# FY_-_OPTO_BOARD_1_SWBOTTOP.net
KiCad netlist of a schematic drawn in EAGLE
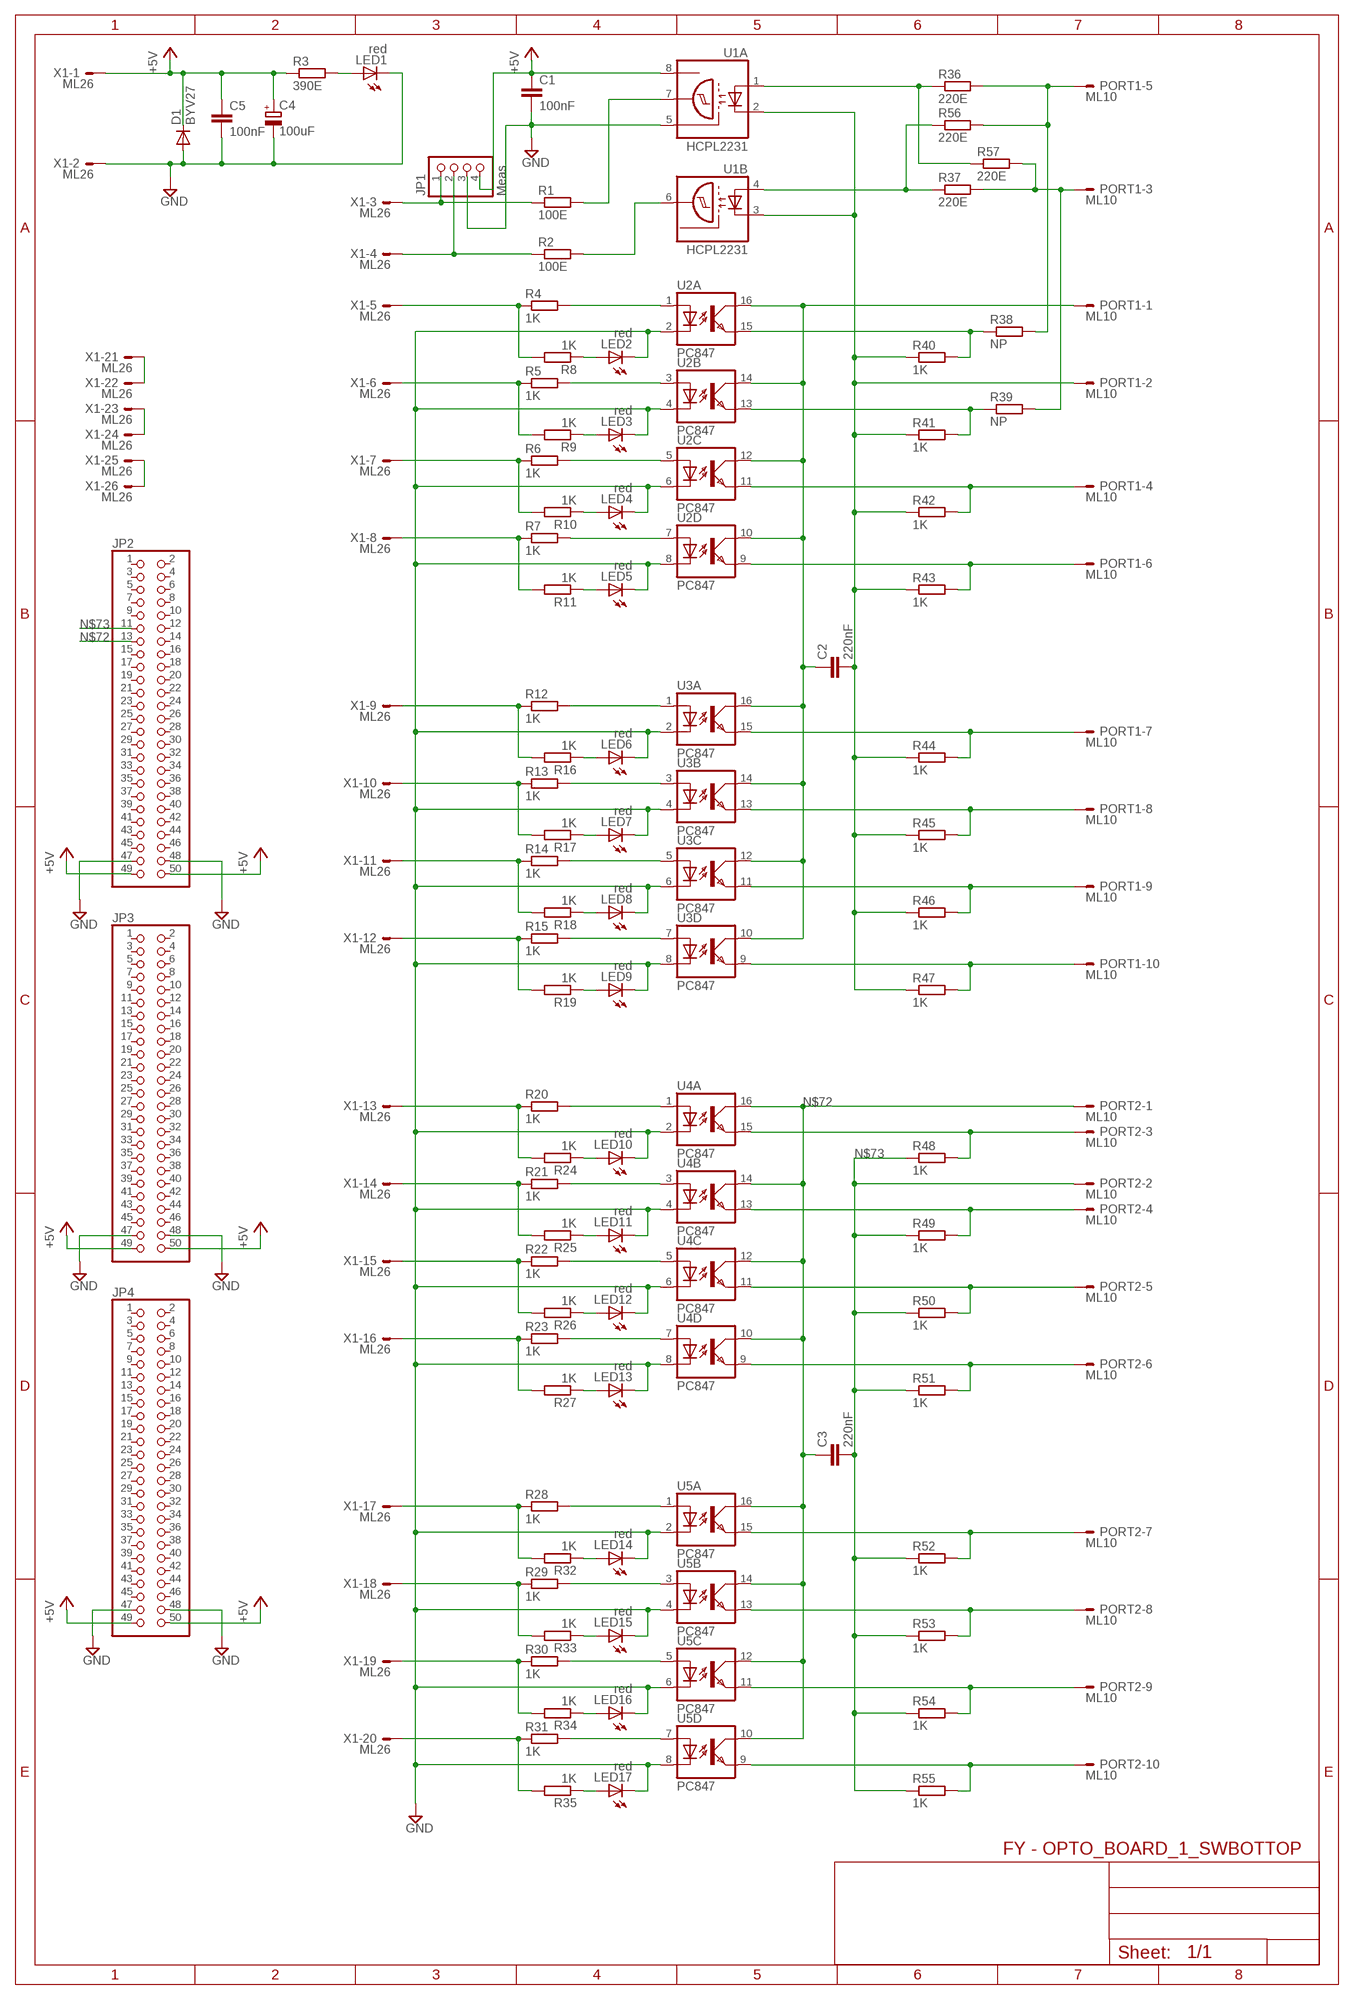
[diagram p0: schematic, sheet 1]

(export (version "E")
  (design (tool "Eeschema 10.0.6"))
  (components
    (comp (ref "C1")
      (value "100nF")
      (footprint "eagle-import:C050-025X075")
      (libsource (lib "eagle-import") (part "C-EU050-025X075"))
    )
    (comp (ref "C2")
      (value "220nF")
      (footprint "eagle-import:C050-025X075")
      (libsource (lib "eagle-import") (part "C-EU050-025X075"))
    )
    (comp (ref "C3")
      (value "220nF")
      (footprint "eagle-import:C050-025X075")
      (libsource (lib "eagle-import") (part "C-EU050-025X075"))
    )
    (comp (ref "C4")
      (value "100uF")
      (footprint "eagle-import:E5-8,5")
      (libsource (lib "eagle-import") (part "CPOL-EUE5-8.5"))
    )
    (comp (ref "C5")
      (value "100nF")
      (footprint "eagle-import:C050-025X075")
      (libsource (lib "eagle-import") (part "C-EU050-025X075"))
    )
    (comp (ref "D1")
      (value "BYV27")
      (footprint "eagle-import:SOD57-10")
      (libsource (lib "eagle-import") (part "BYV27"))
    )
    (comp (ref "JP1")
      (value "Meas")
      (footprint "eagle-import:1X04")
      (libsource (lib "eagle-import") (part "PINHD-1X4"))
    )
    (comp (ref "JP2")
      (value "PINHD-2X25")
      (footprint "eagle-import:2X25")
      (libsource (lib "eagle-import") (part "PINHD-2X25"))
    )
    (comp (ref "JP3")
      (value "PINHD-2X25")
      (footprint "eagle-import:2X25")
      (libsource (lib "eagle-import") (part "PINHD-2X25"))
    )
    (comp (ref "JP4")
      (value "PINHD-2X25")
      (footprint "eagle-import:2X25")
      (libsource (lib "eagle-import") (part "PINHD-2X25"))
    )
    (comp (ref "LED1")
      (value "red")
      (footprint "eagle-import:LED3MM")
      (libsource (lib "eagle-import") (part "LED3MM"))
    )
    (comp (ref "LED2")
      (value "red")
      (footprint "eagle-import:LED3MM")
      (libsource (lib "eagle-import") (part "LED3MM"))
    )
    (comp (ref "LED3")
      (value "red")
      (footprint "eagle-import:LED3MM")
      (libsource (lib "eagle-import") (part "LED3MM"))
    )
    (comp (ref "LED4")
      (value "red")
      (footprint "eagle-import:LED3MM")
      (libsource (lib "eagle-import") (part "LED3MM"))
    )
    (comp (ref "LED5")
      (value "red")
      (footprint "eagle-import:LED3MM")
      (libsource (lib "eagle-import") (part "LED3MM"))
    )
    (comp (ref "LED6")
      (value "red")
      (footprint "eagle-import:LED3MM")
      (libsource (lib "eagle-import") (part "LED3MM"))
    )
    (comp (ref "LED7")
      (value "red")
      (footprint "eagle-import:LED3MM")
      (libsource (lib "eagle-import") (part "LED3MM"))
    )
    (comp (ref "LED8")
      (value "red")
      (footprint "eagle-import:LED3MM")
      (libsource (lib "eagle-import") (part "LED3MM"))
    )
    (comp (ref "LED9")
      (value "red")
      (footprint "eagle-import:LED3MM")
      (libsource (lib "eagle-import") (part "LED3MM"))
    )
    (comp (ref "LED10")
      (value "red")
      (footprint "eagle-import:LED3MM")
      (libsource (lib "eagle-import") (part "LED3MM"))
    )
    (comp (ref "LED11")
      (value "red")
      (footprint "eagle-import:LED3MM")
      (libsource (lib "eagle-import") (part "LED3MM"))
    )
    (comp (ref "LED12")
      (value "red")
      (footprint "eagle-import:LED3MM")
      (libsource (lib "eagle-import") (part "LED3MM"))
    )
    (comp (ref "LED13")
      (value "red")
      (footprint "eagle-import:LED3MM")
      (libsource (lib "eagle-import") (part "LED3MM"))
    )
    (comp (ref "LED14")
      (value "red")
      (footprint "eagle-import:LED3MM")
      (libsource (lib "eagle-import") (part "LED3MM"))
    )
    (comp (ref "LED15")
      (value "red")
      (footprint "eagle-import:LED3MM")
      (libsource (lib "eagle-import") (part "LED3MM"))
    )
    (comp (ref "LED16")
      (value "red")
      (footprint "eagle-import:LED3MM")
      (libsource (lib "eagle-import") (part "LED3MM"))
    )
    (comp (ref "LED17")
      (value "red")
      (footprint "eagle-import:LED3MM")
      (libsource (lib "eagle-import") (part "LED3MM"))
    )
    (comp (ref "PORT1")
      (value "ML10")
      (footprint "eagle-import:ML10")
      (libsource (lib "eagle-import") (part "ML10?E"))
    )
    (comp (ref "PORT2")
      (value "ML10")
      (footprint "eagle-import:ML10")
      (libsource (lib "eagle-import") (part "ML10?E"))
    )
    (comp (ref "R1")
      (value "100E")
      (footprint "eagle-import:0207_10")
      (libsource (lib "eagle-import") (part "R-EU_0207/10"))
    )
    (comp (ref "R2")
      (value "100E")
      (footprint "eagle-import:0207_10")
      (libsource (lib "eagle-import") (part "R-EU_0207/10"))
    )
    (comp (ref "R3")
      (value "390E")
      (footprint "eagle-import:0207_10")
      (libsource (lib "eagle-import") (part "R-EU_0207/10"))
    )
    (comp (ref "R4")
      (value "1K")
      (footprint "eagle-import:0207_10")
      (libsource (lib "eagle-import") (part "R-EU_0207/10"))
    )
    (comp (ref "R5")
      (value "1K")
      (footprint "eagle-import:0207_10")
      (libsource (lib "eagle-import") (part "R-EU_0207/10"))
    )
    (comp (ref "R6")
      (value "1K")
      (footprint "eagle-import:0207_10")
      (libsource (lib "eagle-import") (part "R-EU_0207/10"))
    )
    (comp (ref "R7")
      (value "1K")
      (footprint "eagle-import:0207_10")
      (libsource (lib "eagle-import") (part "R-EU_0207/10"))
    )
    (comp (ref "R8")
      (value "1K")
      (footprint "eagle-import:0207_10")
      (libsource (lib "eagle-import") (part "R-EU_0207/10"))
    )
    (comp (ref "R9")
      (value "1K")
      (footprint "eagle-import:0207_10")
      (libsource (lib "eagle-import") (part "R-EU_0207/10"))
    )
    (comp (ref "R10")
      (value "1K")
      (footprint "eagle-import:0207_10")
      (libsource (lib "eagle-import") (part "R-EU_0207/10"))
    )
    (comp (ref "R11")
      (value "1K")
      (footprint "eagle-import:0207_10")
      (libsource (lib "eagle-import") (part "R-EU_0207/10"))
    )
    (comp (ref "R12")
      (value "1K")
      (footprint "eagle-import:0207_10")
      (libsource (lib "eagle-import") (part "R-EU_0207/10"))
    )
    (comp (ref "R13")
      (value "1K")
      (footprint "eagle-import:0207_10")
      (libsource (lib "eagle-import") (part "R-EU_0207/10"))
    )
    (comp (ref "R14")
      (value "1K")
      (footprint "eagle-import:0207_10")
      (libsource (lib "eagle-import") (part "R-EU_0207/10"))
    )
    (comp (ref "R15")
      (value "1K")
      (footprint "eagle-import:0207_10")
      (libsource (lib "eagle-import") (part "R-EU_0207/10"))
    )
    (comp (ref "R16")
      (value "1K")
      (footprint "eagle-import:0207_10")
      (libsource (lib "eagle-import") (part "R-EU_0207/10"))
    )
    (comp (ref "R17")
      (value "1K")
      (footprint "eagle-import:0207_10")
      (libsource (lib "eagle-import") (part "R-EU_0207/10"))
    )
    (comp (ref "R18")
      (value "1K")
      (footprint "eagle-import:0207_10")
      (libsource (lib "eagle-import") (part "R-EU_0207/10"))
    )
    (comp (ref "R19")
      (value "1K")
      (footprint "eagle-import:0207_10")
      (libsource (lib "eagle-import") (part "R-EU_0207/10"))
    )
    (comp (ref "R20")
      (value "1K")
      (footprint "eagle-import:0207_10")
      (libsource (lib "eagle-import") (part "R-EU_0207/10"))
    )
    (comp (ref "R21")
      (value "1K")
      (footprint "eagle-import:0207_10")
      (libsource (lib "eagle-import") (part "R-EU_0207/10"))
    )
    (comp (ref "R22")
      (value "1K")
      (footprint "eagle-import:0207_10")
      (libsource (lib "eagle-import") (part "R-EU_0207/10"))
    )
    (comp (ref "R23")
      (value "1K")
      (footprint "eagle-import:0207_10")
      (libsource (lib "eagle-import") (part "R-EU_0207/10"))
    )
    (comp (ref "R24")
      (value "1K")
      (footprint "eagle-import:0207_10")
      (libsource (lib "eagle-import") (part "R-EU_0207/10"))
    )
    (comp (ref "R25")
      (value "1K")
      (footprint "eagle-import:0207_10")
      (libsource (lib "eagle-import") (part "R-EU_0207/10"))
    )
    (comp (ref "R26")
      (value "1K")
      (footprint "eagle-import:0207_10")
      (libsource (lib "eagle-import") (part "R-EU_0207/10"))
    )
    (comp (ref "R27")
      (value "1K")
      (footprint "eagle-import:0207_10")
      (libsource (lib "eagle-import") (part "R-EU_0207/10"))
    )
    (comp (ref "R28")
      (value "1K")
      (footprint "eagle-import:0207_10")
      (libsource (lib "eagle-import") (part "R-EU_0207/10"))
    )
    (comp (ref "R29")
      (value "1K")
      (footprint "eagle-import:0207_10")
      (libsource (lib "eagle-import") (part "R-EU_0207/10"))
    )
    (comp (ref "R30")
      (value "1K")
      (footprint "eagle-import:0207_10")
      (libsource (lib "eagle-import") (part "R-EU_0207/10"))
    )
    (comp (ref "R31")
      (value "1K")
      (footprint "eagle-import:0207_10")
      (libsource (lib "eagle-import") (part "R-EU_0207/10"))
    )
    (comp (ref "R32")
      (value "1K")
      (footprint "eagle-import:0207_10")
      (libsource (lib "eagle-import") (part "R-EU_0207/10"))
    )
    (comp (ref "R33")
      (value "1K")
      (footprint "eagle-import:0207_10")
      (libsource (lib "eagle-import") (part "R-EU_0207/10"))
    )
    (comp (ref "R34")
      (value "1K")
      (footprint "eagle-import:0207_10")
      (libsource (lib "eagle-import") (part "R-EU_0207/10"))
    )
    (comp (ref "R35")
      (value "1K")
      (footprint "eagle-import:0207_10")
      (libsource (lib "eagle-import") (part "R-EU_0207/10"))
    )
    (comp (ref "R36")
      (value "220E")
      (footprint "eagle-import:0207_10")
      (libsource (lib "eagle-import") (part "R-EU_0207/10"))
    )
    (comp (ref "R37")
      (value "220E")
      (footprint "eagle-import:0207_10")
      (libsource (lib "eagle-import") (part "R-EU_0207/10"))
    )
    (comp (ref "R38")
      (value "NP")
      (footprint "eagle-import:0207_10")
      (libsource (lib "eagle-import") (part "R-EU_0207/10"))
    )
    (comp (ref "R39")
      (value "NP")
      (footprint "eagle-import:0207_10")
      (libsource (lib "eagle-import") (part "R-EU_0207/10"))
    )
    (comp (ref "R40")
      (value "1K")
      (footprint "eagle-import:0207_10")
      (libsource (lib "eagle-import") (part "R-EU_0207/10"))
    )
    (comp (ref "R41")
      (value "1K")
      (footprint "eagle-import:0207_10")
      (libsource (lib "eagle-import") (part "R-EU_0207/10"))
    )
    (comp (ref "R42")
      (value "1K")
      (footprint "eagle-import:0207_10")
      (libsource (lib "eagle-import") (part "R-EU_0207/10"))
    )
    (comp (ref "R43")
      (value "1K")
      (footprint "eagle-import:0207_10")
      (libsource (lib "eagle-import") (part "R-EU_0207/10"))
    )
    (comp (ref "R44")
      (value "1K")
      (footprint "eagle-import:0207_10")
      (libsource (lib "eagle-import") (part "R-EU_0207/10"))
    )
    (comp (ref "R45")
      (value "1K")
      (footprint "eagle-import:0207_10")
      (libsource (lib "eagle-import") (part "R-EU_0207/10"))
    )
    (comp (ref "R46")
      (value "1K")
      (footprint "eagle-import:0207_10")
      (libsource (lib "eagle-import") (part "R-EU_0207/10"))
    )
    (comp (ref "R47")
      (value "1K")
      (footprint "eagle-import:0207_10")
      (libsource (lib "eagle-import") (part "R-EU_0207/10"))
    )
    (comp (ref "R48")
      (value "1K")
      (footprint "eagle-import:0207_10")
      (libsource (lib "eagle-import") (part "R-EU_0207/10"))
    )
    (comp (ref "R49")
      (value "1K")
      (footprint "eagle-import:0207_10")
      (libsource (lib "eagle-import") (part "R-EU_0207/10"))
    )
    (comp (ref "R50")
      (value "1K")
      (footprint "eagle-import:0207_10")
      (libsource (lib "eagle-import") (part "R-EU_0207/10"))
    )
    (comp (ref "R51")
      (value "1K")
      (footprint "eagle-import:0207_10")
      (libsource (lib "eagle-import") (part "R-EU_0207/10"))
    )
    (comp (ref "R52")
      (value "1K")
      (footprint "eagle-import:0207_10")
      (libsource (lib "eagle-import") (part "R-EU_0207/10"))
    )
    (comp (ref "R53")
      (value "1K")
      (footprint "eagle-import:0207_10")
      (libsource (lib "eagle-import") (part "R-EU_0207/10"))
    )
    (comp (ref "R54")
      (value "1K")
      (footprint "eagle-import:0207_10")
      (libsource (lib "eagle-import") (part "R-EU_0207/10"))
    )
    (comp (ref "R55")
      (value "1K")
      (footprint "eagle-import:0207_10")
      (libsource (lib "eagle-import") (part "R-EU_0207/10"))
    )
    (comp (ref "R56")
      (value "220E")
      (footprint "eagle-import:0207_10")
      (libsource (lib "eagle-import") (part "R-EU_0207/10"))
    )
    (comp (ref "R57")
      (value "220E")
      (footprint "eagle-import:0207_10")
      (libsource (lib "eagle-import") (part "R-EU_0207/10"))
    )
    (comp (ref "U1")
      (value "HCPL2231")
      (footprint "eagle-import:DIL08")
      (fields (field (name "MF") "AGILENT TECHNOLOGIES") (field (name "MPN") "HCPL-2231-000E"))
      (libsource (lib "eagle-import") (part "HCPL2231"))
    )
    (comp (ref "U2")
      (value "PC847")
      (footprint "eagle-import:DIL16")
      (libsource (lib "eagle-import") (part "PC847"))
    )
    (comp (ref "U3")
      (value "PC847")
      (footprint "eagle-import:DIL16")
      (libsource (lib "eagle-import") (part "PC847"))
    )
    (comp (ref "U4")
      (value "PC847")
      (footprint "eagle-import:DIL16")
      (libsource (lib "eagle-import") (part "PC847"))
    )
    (comp (ref "U5")
      (value "PC847")
      (footprint "eagle-import:DIL16")
      (libsource (lib "eagle-import") (part "PC847"))
    )
    (comp (ref "X1")
      (value "ML26")
      (footprint "eagle-import:ML26")
      (libsource (lib "eagle-import") (part "ML26?E"))
    )
  )
  (nets
    (net (code "1") (name "+5V") (class "Default")
      (node (ref "C1") (pin "1") (pinfunction "1_1") (pintype "passive"))
      (node (ref "C4") (pin "+") (pinfunction "+_+") (pintype "passive"))
      (node (ref "C5") (pin "1") (pinfunction "1_1") (pintype "passive"))
      (node (ref "D1") (pin "C") (pinfunction "C_C") (pintype "passive"))
      (node (ref "JP1") (pin "4") (pinfunction "4_4") (pintype "passive"))
      (node (ref "JP2") (pin "49") (pinfunction "49_49") (pintype "passive"))
      (node (ref "JP2") (pin "50") (pinfunction "50_50") (pintype "passive"))
      (node (ref "JP3") (pin "49") (pinfunction "49_49") (pintype "passive"))
      (node (ref "JP3") (pin "50") (pinfunction "50_50") (pintype "passive"))
      (node (ref "JP4") (pin "49") (pinfunction "49_49") (pintype "passive"))
      (node (ref "JP4") (pin "50") (pinfunction "50_50") (pintype "passive"))
      (node (ref "R3") (pin "1") (pinfunction "1_1") (pintype "passive"))
      (node (ref "U1") (pin "8") (pinfunction "VCC_8") (pintype "passive"))
      (node (ref "X1") (pin "1") (pinfunction "S_1") (pintype "passive"))
    )
    (net (code "2") (name "/N$72") (class "Default")
      (node (ref "C3") (pin "1") (pinfunction "1_1") (pintype "passive"))
      (node (ref "JP2") (pin "13") (pinfunction "13_13") (pintype "passive"))
      (node (ref "PORT2") (pin "1") (pinfunction "S_1") (pintype "passive"))
      (node (ref "U4") (pin "10") (pinfunction "COL_10") (pintype "passive"))
      (node (ref "U4") (pin "12") (pinfunction "COL_12") (pintype "passive"))
      (node (ref "U4") (pin "14") (pinfunction "COL_14") (pintype "passive"))
      (node (ref "U4") (pin "16") (pinfunction "COL_16") (pintype "passive"))
      (node (ref "U5") (pin "10") (pinfunction "COL_10") (pintype "passive"))
      (node (ref "U5") (pin "12") (pinfunction "COL_12") (pintype "passive"))
      (node (ref "U5") (pin "14") (pinfunction "COL_14") (pintype "passive"))
      (node (ref "U5") (pin "16") (pinfunction "COL_16") (pintype "passive"))
    )
    (net (code "3") (name "/N$73") (class "Default")
      (node (ref "C3") (pin "2") (pinfunction "2_2") (pintype "passive"))
      (node (ref "JP2") (pin "11") (pinfunction "11_11") (pintype "passive"))
      (node (ref "PORT2") (pin "2") (pinfunction "S_2") (pintype "passive"))
      (node (ref "R48") (pin "1") (pinfunction "1_1") (pintype "passive"))
      (node (ref "R49") (pin "1") (pinfunction "1_1") (pintype "passive"))
      (node (ref "R50") (pin "1") (pinfunction "1_1") (pintype "passive"))
      (node (ref "R51") (pin "1") (pinfunction "1_1") (pintype "passive"))
      (node (ref "R52") (pin "1") (pinfunction "1_1") (pintype "passive"))
      (node (ref "R53") (pin "1") (pinfunction "1_1") (pintype "passive"))
      (node (ref "R54") (pin "1") (pinfunction "1_1") (pintype "passive"))
      (node (ref "R55") (pin "1") (pinfunction "1_1") (pintype "passive"))
    )
    (net (code "4") (name "GND") (class "Default")
      (node (ref "C1") (pin "2") (pinfunction "2_2") (pintype "passive"))
      (node (ref "C4") (pin "-") (pinfunction "-_-") (pintype "passive"))
      (node (ref "C5") (pin "2") (pinfunction "2_2") (pintype "passive"))
      (node (ref "D1") (pin "A") (pinfunction "A_A") (pintype "passive"))
      (node (ref "JP1") (pin "3") (pinfunction "3_3") (pintype "passive"))
      (node (ref "JP2") (pin "47") (pinfunction "47_47") (pintype "passive"))
      (node (ref "JP2") (pin "48") (pinfunction "48_48") (pintype "passive"))
      (node (ref "JP3") (pin "47") (pinfunction "47_47") (pintype "passive"))
      (node (ref "JP3") (pin "48") (pinfunction "48_48") (pintype "passive"))
      (node (ref "JP4") (pin "47") (pinfunction "47_47") (pintype "passive"))
      (node (ref "JP4") (pin "48") (pinfunction "48_48") (pintype "passive"))
      (node (ref "LED1") (pin "K") (pinfunction "C_K") (pintype "passive"))
      (node (ref "LED10") (pin "K") (pinfunction "C_K") (pintype "passive"))
      (node (ref "LED11") (pin "K") (pinfunction "C_K") (pintype "passive"))
      (node (ref "LED12") (pin "K") (pinfunction "C_K") (pintype "passive"))
      (node (ref "LED13") (pin "K") (pinfunction "C_K") (pintype "passive"))
      (node (ref "LED14") (pin "K") (pinfunction "C_K") (pintype "passive"))
      (node (ref "LED15") (pin "K") (pinfunction "C_K") (pintype "passive"))
      (node (ref "LED16") (pin "K") (pinfunction "C_K") (pintype "passive"))
      (node (ref "LED17") (pin "K") (pinfunction "C_K") (pintype "passive"))
      (node (ref "LED2") (pin "K") (pinfunction "C_K") (pintype "passive"))
      (node (ref "LED3") (pin "K") (pinfunction "C_K") (pintype "passive"))
      (node (ref "LED4") (pin "K") (pinfunction "C_K") (pintype "passive"))
      (node (ref "LED5") (pin "K") (pinfunction "C_K") (pintype "passive"))
      (node (ref "LED6") (pin "K") (pinfunction "C_K") (pintype "passive"))
      (node (ref "LED7") (pin "K") (pinfunction "C_K") (pintype "passive"))
      (node (ref "LED8") (pin "K") (pinfunction "C_K") (pintype "passive"))
      (node (ref "LED9") (pin "K") (pinfunction "C_K") (pintype "passive"))
      (node (ref "U1") (pin "5") (pinfunction "GND_5") (pintype "passive"))
      (node (ref "U2") (pin "2") (pinfunction "C_2") (pintype "passive"))
      (node (ref "U2") (pin "4") (pinfunction "C_4") (pintype "passive"))
      (node (ref "U2") (pin "6") (pinfunction "C_6") (pintype "passive"))
      (node (ref "U2") (pin "8") (pinfunction "C_8") (pintype "passive"))
      (node (ref "U3") (pin "2") (pinfunction "C_2") (pintype "passive"))
      (node (ref "U3") (pin "4") (pinfunction "C_4") (pintype "passive"))
      (node (ref "U3") (pin "6") (pinfunction "C_6") (pintype "passive"))
      (node (ref "U3") (pin "8") (pinfunction "C_8") (pintype "passive"))
      (node (ref "U4") (pin "2") (pinfunction "C_2") (pintype "passive"))
      (node (ref "U4") (pin "4") (pinfunction "C_4") (pintype "passive"))
      (node (ref "U4") (pin "6") (pinfunction "C_6") (pintype "passive"))
      (node (ref "U4") (pin "8") (pinfunction "C_8") (pintype "passive"))
      (node (ref "U5") (pin "2") (pinfunction "C_2") (pintype "passive"))
      (node (ref "U5") (pin "4") (pinfunction "C_4") (pintype "passive"))
      (node (ref "U5") (pin "6") (pinfunction "C_6") (pintype "passive"))
      (node (ref "U5") (pin "8") (pinfunction "C_8") (pintype "passive"))
      (node (ref "X1") (pin "2") (pinfunction "S_2") (pintype "passive"))
    )
    (net (code "5") (name "Net-(LED1-PadA)") (class "Default")
      (node (ref "LED1") (pin "A") (pinfunction "A_A") (pintype "passive"))
      (node (ref "R3") (pin "2") (pinfunction "2_2") (pintype "passive"))
    )
    (net (code "6") (name "Net-(LED2-PadA)") (class "Default")
      (node (ref "LED2") (pin "A") (pinfunction "A_A") (pintype "passive"))
      (node (ref "R8") (pin "1") (pinfunction "1_1") (pintype "passive"))
    )
    (net (code "7") (name "Net-(LED3-PadA)") (class "Default")
      (node (ref "LED3") (pin "A") (pinfunction "A_A") (pintype "passive"))
      (node (ref "R9") (pin "1") (pinfunction "1_1") (pintype "passive"))
    )
    (net (code "8") (name "Net-(LED4-PadA)") (class "Default")
      (node (ref "LED4") (pin "A") (pinfunction "A_A") (pintype "passive"))
      (node (ref "R10") (pin "1") (pinfunction "1_1") (pintype "passive"))
    )
    (net (code "9") (name "Net-(LED5-PadA)") (class "Default")
      (node (ref "LED5") (pin "A") (pinfunction "A_A") (pintype "passive"))
      (node (ref "R11") (pin "1") (pinfunction "1_1") (pintype "passive"))
    )
    (net (code "10") (name "Net-(LED6-PadA)") (class "Default")
      (node (ref "LED6") (pin "A") (pinfunction "A_A") (pintype "passive"))
      (node (ref "R16") (pin "1") (pinfunction "1_1") (pintype "passive"))
    )
    (net (code "11") (name "Net-(LED7-PadA)") (class "Default")
      (node (ref "LED7") (pin "A") (pinfunction "A_A") (pintype "passive"))
      (node (ref "R17") (pin "1") (pinfunction "1_1") (pintype "passive"))
    )
    (net (code "12") (name "Net-(LED8-PadA)") (class "Default")
      (node (ref "LED8") (pin "A") (pinfunction "A_A") (pintype "passive"))
      (node (ref "R18") (pin "1") (pinfunction "1_1") (pintype "passive"))
    )
    (net (code "13") (name "Net-(LED9-PadA)") (class "Default")
      (node (ref "LED9") (pin "A") (pinfunction "A_A") (pintype "passive"))
      (node (ref "R19") (pin "1") (pinfunction "1_1") (pintype "passive"))
    )
    (net (code "14") (name "Net-(LED10-PadA)") (class "Default")
      (node (ref "LED10") (pin "A") (pinfunction "A_A") (pintype "passive"))
      (node (ref "R24") (pin "1") (pinfunction "1_1") (pintype "passive"))
    )
    (net (code "15") (name "Net-(LED11-PadA)") (class "Default")
      (node (ref "LED11") (pin "A") (pinfunction "A_A") (pintype "passive"))
      (node (ref "R25") (pin "1") (pinfunction "1_1") (pintype "passive"))
    )
    (net (code "16") (name "Net-(LED12-PadA)") (class "Default")
      (node (ref "LED12") (pin "A") (pinfunction "A_A") (pintype "passive"))
      (node (ref "R26") (pin "1") (pinfunction "1_1") (pintype "passive"))
    )
    (net (code "17") (name "Net-(LED13-PadA)") (class "Default")
      (node (ref "LED13") (pin "A") (pinfunction "A_A") (pintype "passive"))
      (node (ref "R27") (pin "1") (pinfunction "1_1") (pintype "passive"))
    )
    (net (code "18") (name "Net-(LED14-PadA)") (class "Default")
      (node (ref "LED14") (pin "A") (pinfunction "A_A") (pintype "passive"))
      (node (ref "R32") (pin "1") (pinfunction "1_1") (pintype "passive"))
    )
    (net (code "19") (name "Net-(LED15-PadA)") (class "Default")
      (node (ref "LED15") (pin "A") (pinfunction "A_A") (pintype "passive"))
      (node (ref "R33") (pin "1") (pinfunction "1_1") (pintype "passive"))
    )
    (net (code "20") (name "Net-(LED16-PadA)") (class "Default")
      (node (ref "LED16") (pin "A") (pinfunction "A_A") (pintype "passive"))
      (node (ref "R34") (pin "1") (pinfunction "1_1") (pintype "passive"))
    )
    (net (code "21") (name "Net-(LED17-PadA)") (class "Default")
      (node (ref "LED17") (pin "A") (pinfunction "A_A") (pintype "passive"))
      (node (ref "R35") (pin "1") (pinfunction "1_1") (pintype "passive"))
    )
    (net (code "22") (name "Net-(PORT1A-S)") (class "Default")
      (node (ref "C2") (pin "1") (pinfunction "1_1") (pintype "passive"))
      (node (ref "PORT1") (pin "1") (pinfunction "S_1") (pintype "passive"))
      (node (ref "U2") (pin "10") (pinfunction "COL_10") (pintype "passive"))
      (node (ref "U2") (pin "12") (pinfunction "COL_12") (pintype "passive"))
      (node (ref "U2") (pin "14") (pinfunction "COL_14") (pintype "passive"))
      (node (ref "U2") (pin "16") (pinfunction "COL_16") (pintype "passive"))
      (node (ref "U3") (pin "10") (pinfunction "COL_10") (pintype "passive"))
      (node (ref "U3") (pin "12") (pinfunction "COL_12") (pintype "passive"))
      (node (ref "U3") (pin "14") (pinfunction "COL_14") (pintype "passive"))
      (node (ref "U3") (pin "16") (pinfunction "COL_16") (pintype "passive"))
    )
    (net (code "23") (name "Net-(PORT1B-S)") (class "Default")
      (node (ref "PORT1") (pin "10") (pinfunction "S_10") (pintype "passive"))
      (node (ref "R47") (pin "2") (pinfunction "2_2") (pintype "passive"))
      (node (ref "U3") (pin "9") (pinfunction "EMIT_9") (pintype "passive"))
    )
    (net (code "24") (name "Net-(PORT1C-S)") (class "Default")
      (node (ref "C2") (pin "2") (pinfunction "2_2") (pintype "passive"))
      (node (ref "PORT1") (pin "2") (pinfunction "S_2") (pintype "passive"))
      (node (ref "R40") (pin "1") (pinfunction "1_1") (pintype "passive"))
      (node (ref "R41") (pin "1") (pinfunction "1_1") (pintype "passive"))
      (node (ref "R42") (pin "1") (pinfunction "1_1") (pintype "passive"))
      (node (ref "R43") (pin "1") (pinfunction "1_1") (pintype "passive"))
      (node (ref "R44") (pin "1") (pinfunction "1_1") (pintype "passive"))
      (node (ref "R45") (pin "1") (pinfunction "1_1") (pintype "passive"))
      (node (ref "R46") (pin "1") (pinfunction "1_1") (pintype "passive"))
      (node (ref "R47") (pin "1") (pinfunction "1_1") (pintype "passive"))
      (node (ref "U1") (pin "2") (pinfunction "C_2") (pintype "passive"))
      (node (ref "U1") (pin "3") (pinfunction "C_3") (pintype "passive"))
    )
    (net (code "25") (name "Net-(PORT1D-S)") (class "Default")
      (node (ref "PORT1") (pin "3") (pinfunction "S_3") (pintype "passive"))
      (node (ref "R37") (pin "2") (pinfunction "2_2") (pintype "passive"))
      (node (ref "R39") (pin "2") (pinfunction "2_2") (pintype "passive"))
      (node (ref "R57") (pin "2") (pinfunction "2_2") (pintype "passive"))
    )
    (net (code "26") (name "Net-(PORT1E-S)") (class "Default")
      (node (ref "PORT1") (pin "4") (pinfunction "S_4") (pintype "passive"))
      (node (ref "R42") (pin "2") (pinfunction "2_2") (pintype "passive"))
      (node (ref "U2") (pin "11") (pinfunction "EMIT_11") (pintype "passive"))
    )
    (net (code "27") (name "Net-(PORT1F-S)") (class "Default")
      (node (ref "PORT1") (pin "5") (pinfunction "S_5") (pintype "passive"))
      (node (ref "R36") (pin "2") (pinfunction "2_2") (pintype "passive"))
      (node (ref "R38") (pin "2") (pinfunction "2_2") (pintype "passive"))
      (node (ref "R56") (pin "2") (pinfunction "2_2") (pintype "passive"))
    )
    (net (code "28") (name "Net-(PORT1G-S)") (class "Default")
      (node (ref "PORT1") (pin "6") (pinfunction "S_6") (pintype "passive"))
      (node (ref "R43") (pin "2") (pinfunction "2_2") (pintype "passive"))
      (node (ref "U2") (pin "9") (pinfunction "EMIT_9") (pintype "passive"))
    )
    (net (code "29") (name "Net-(PORT1H-S)") (class "Default")
      (node (ref "PORT1") (pin "7") (pinfunction "S_7") (pintype "passive"))
      (node (ref "R44") (pin "2") (pinfunction "2_2") (pintype "passive"))
      (node (ref "U3") (pin "15") (pinfunction "EMIT_15") (pintype "passive"))
    )
    (net (code "30") (name "Net-(PORT1I-S)") (class "Default")
      (node (ref "PORT1") (pin "8") (pinfunction "S_8") (pintype "passive"))
      (node (ref "R45") (pin "2") (pinfunction "2_2") (pintype "passive"))
      (node (ref "U3") (pin "13") (pinfunction "EMIT_13") (pintype "passive"))
    )
    (net (code "31") (name "Net-(PORT1J-S)") (class "Default")
      (node (ref "PORT1") (pin "9") (pinfunction "S_9") (pintype "passive"))
      (node (ref "R46") (pin "2") (pinfunction "2_2") (pintype "passive"))
      (node (ref "U3") (pin "11") (pinfunction "EMIT_11") (pintype "passive"))
    )
    (net (code "32") (name "Net-(PORT2B-S)") (class "Default")
      (node (ref "PORT2") (pin "10") (pinfunction "S_10") (pintype "passive"))
      (node (ref "R55") (pin "2") (pinfunction "2_2") (pintype "passive"))
      (node (ref "U5") (pin "9") (pinfunction "EMIT_9") (pintype "passive"))
    )
    (net (code "33") (name "Net-(PORT2D-S)") (class "Default")
      (node (ref "PORT2") (pin "3") (pinfunction "S_3") (pintype "passive"))
      (node (ref "R48") (pin "2") (pinfunction "2_2") (pintype "passive"))
      (node (ref "U4") (pin "15") (pinfunction "EMIT_15") (pintype "passive"))
    )
    (net (code "34") (name "Net-(PORT2E-S)") (class "Default")
      (node (ref "PORT2") (pin "4") (pinfunction "S_4") (pintype "passive"))
      (node (ref "R49") (pin "2") (pinfunction "2_2") (pintype "passive"))
      (node (ref "U4") (pin "13") (pinfunction "EMIT_13") (pintype "passive"))
    )
    (net (code "35") (name "Net-(PORT2F-S)") (class "Default")
      (node (ref "PORT2") (pin "5") (pinfunction "S_5") (pintype "passive"))
      (node (ref "R50") (pin "2") (pinfunction "2_2") (pintype "passive"))
      (node (ref "U4") (pin "11") (pinfunction "EMIT_11") (pintype "passive"))
    )
    (net (code "36") (name "Net-(PORT2G-S)") (class "Default")
      (node (ref "PORT2") (pin "6") (pinfunction "S_6") (pintype "passive"))
      (node (ref "R51") (pin "2") (pinfunction "2_2") (pintype "passive"))
      (node (ref "U4") (pin "9") (pinfunction "EMIT_9") (pintype "passive"))
    )
    (net (code "37") (name "Net-(PORT2H-S)") (class "Default")
      (node (ref "PORT2") (pin "7") (pinfunction "S_7") (pintype "passive"))
      (node (ref "R52") (pin "2") (pinfunction "2_2") (pintype "passive"))
      (node (ref "U5") (pin "15") (pinfunction "EMIT_15") (pintype "passive"))
    )
    (net (code "38") (name "Net-(PORT2I-S)") (class "Default")
      (node (ref "PORT2") (pin "8") (pinfunction "S_8") (pintype "passive"))
      (node (ref "R53") (pin "2") (pinfunction "2_2") (pintype "passive"))
      (node (ref "U5") (pin "13") (pinfunction "EMIT_13") (pintype "passive"))
    )
    (net (code "39") (name "Net-(PORT2J-S)") (class "Default")
      (node (ref "PORT2") (pin "9") (pinfunction "S_9") (pintype "passive"))
      (node (ref "R54") (pin "2") (pinfunction "2_2") (pintype "passive"))
      (node (ref "U5") (pin "11") (pinfunction "EMIT_11") (pintype "passive"))
    )
    (net (code "40") (name "Net-(U1A-A)") (class "Default")
      (node (ref "R36") (pin "1") (pinfunction "1_1") (pintype "passive"))
      (node (ref "R57") (pin "1") (pinfunction "1_1") (pintype "passive"))
      (node (ref "U1") (pin "1") (pinfunction "A_1") (pintype "passive"))
    )
    (net (code "41") (name "Net-(U1A-OUT)") (class "Default")
      (node (ref "R1") (pin "2") (pinfunction "2_2") (pintype "passive"))
      (node (ref "U1") (pin "7") (pinfunction "OUT_7") (pintype "passive"))
    )
    (net (code "42") (name "Net-(U1B-A)") (class "Default")
      (node (ref "R37") (pin "1") (pinfunction "1_1") (pintype "passive"))
      (node (ref "R56") (pin "1") (pinfunction "1_1") (pintype "passive"))
      (node (ref "U1") (pin "4") (pinfunction "A_4") (pintype "passive"))
    )
    (net (code "43") (name "Net-(U1B-OUT)") (class "Default")
      (node (ref "R2") (pin "2") (pinfunction "2_2") (pintype "passive"))
      (node (ref "U1") (pin "6") (pinfunction "OUT_6") (pintype "passive"))
    )
    (net (code "44") (name "Net-(U2A-A)") (class "Default")
      (node (ref "R4") (pin "2") (pinfunction "2_2") (pintype "passive"))
      (node (ref "U2") (pin "1") (pinfunction "A_1") (pintype "passive"))
    )
    (net (code "45") (name "Net-(U2A-EMIT)") (class "Default")
      (node (ref "R38") (pin "1") (pinfunction "1_1") (pintype "passive"))
      (node (ref "R40") (pin "2") (pinfunction "2_2") (pintype "passive"))
      (node (ref "U2") (pin "15") (pinfunction "EMIT_15") (pintype "passive"))
    )
    (net (code "46") (name "Net-(U2B-A)") (class "Default")
      (node (ref "R5") (pin "2") (pinfunction "2_2") (pintype "passive"))
      (node (ref "U2") (pin "3") (pinfunction "A_3") (pintype "passive"))
    )
    (net (code "47") (name "Net-(U2B-EMIT)") (class "Default")
      (node (ref "R39") (pin "1") (pinfunction "1_1") (pintype "passive"))
      (node (ref "R41") (pin "2") (pinfunction "2_2") (pintype "passive"))
      (node (ref "U2") (pin "13") (pinfunction "EMIT_13") (pintype "passive"))
    )
    (net (code "48") (name "Net-(U2C-A)") (class "Default")
      (node (ref "R6") (pin "2") (pinfunction "2_2") (pintype "passive"))
      (node (ref "U2") (pin "5") (pinfunction "A_5") (pintype "passive"))
    )
    (net (code "49") (name "Net-(U2D-A)") (class "Default")
      (node (ref "R7") (pin "2") (pinfunction "2_2") (pintype "passive"))
      (node (ref "U2") (pin "7") (pinfunction "A_7") (pintype "passive"))
    )
    (net (code "50") (name "Net-(U3A-A)") (class "Default")
      (node (ref "R12") (pin "2") (pinfunction "2_2") (pintype "passive"))
      (node (ref "U3") (pin "1") (pinfunction "A_1") (pintype "passive"))
    )
    (net (code "51") (name "Net-(U3B-A)") (class "Default")
      (node (ref "R13") (pin "2") (pinfunction "2_2") (pintype "passive"))
      (node (ref "U3") (pin "3") (pinfunction "A_3") (pintype "passive"))
    )
    (net (code "52") (name "Net-(U3C-A)") (class "Default")
      (node (ref "R14") (pin "2") (pinfunction "2_2") (pintype "passive"))
      (node (ref "U3") (pin "5") (pinfunction "A_5") (pintype "passive"))
    )
    (net (code "53") (name "Net-(U3D-A)") (class "Default")
      (node (ref "R15") (pin "2") (pinfunction "2_2") (pintype "passive"))
      (node (ref "U3") (pin "7") (pinfunction "A_7") (pintype "passive"))
    )
    (net (code "54") (name "Net-(U4A-A)") (class "Default")
      (node (ref "R20") (pin "2") (pinfunction "2_2") (pintype "passive"))
      (node (ref "U4") (pin "1") (pinfunction "A_1") (pintype "passive"))
    )
    (net (code "55") (name "Net-(U4B-A)") (class "Default")
      (node (ref "R21") (pin "2") (pinfunction "2_2") (pintype "passive"))
      (node (ref "U4") (pin "3") (pinfunction "A_3") (pintype "passive"))
    )
    (net (code "56") (name "Net-(U4C-A)") (class "Default")
      (node (ref "R22") (pin "2") (pinfunction "2_2") (pintype "passive"))
      (node (ref "U4") (pin "5") (pinfunction "A_5") (pintype "passive"))
    )
    (net (code "57") (name "Net-(U4D-A)") (class "Default")
      (node (ref "R23") (pin "2") (pinfunction "2_2") (pintype "passive"))
      (node (ref "U4") (pin "7") (pinfunction "A_7") (pintype "passive"))
    )
    (net (code "58") (name "Net-(U5A-A)") (class "Default")
      (node (ref "R28") (pin "2") (pinfunction "2_2") (pintype "passive"))
      (node (ref "U5") (pin "1") (pinfunction "A_1") (pintype "passive"))
    )
    (net (code "59") (name "Net-(U5B-A)") (class "Default")
      (node (ref "R29") (pin "2") (pinfunction "2_2") (pintype "passive"))
      (node (ref "U5") (pin "3") (pinfunction "A_3") (pintype "passive"))
    )
    (net (code "60") (name "Net-(U5C-A)") (class "Default")
      (node (ref "R30") (pin "2") (pinfunction "2_2") (pintype "passive"))
      (node (ref "U5") (pin "5") (pinfunction "A_5") (pintype "passive"))
    )
    (net (code "61") (name "Net-(U5D-A)") (class "Default")
      (node (ref "R31") (pin "2") (pinfunction "2_2") (pintype "passive"))
      (node (ref "U5") (pin "7") (pinfunction "A_7") (pintype "passive"))
    )
    (net (code "62") (name "Net-(X1B-S)") (class "Default")
      (node (ref "R13") (pin "1") (pinfunction "1_1") (pintype "passive"))
      (node (ref "R17") (pin "2") (pinfunction "2_2") (pintype "passive"))
      (node (ref "X1") (pin "10") (pinfunction "S_10") (pintype "passive"))
    )
    (net (code "63") (name "Net-(X1C-S)") (class "Default")
      (node (ref "R14") (pin "1") (pinfunction "1_1") (pintype "passive"))
      (node (ref "R18") (pin "2") (pinfunction "2_2") (pintype "passive"))
      (node (ref "X1") (pin "11") (pinfunction "S_11") (pintype "passive"))
    )
    (net (code "64") (name "Net-(X1D-S)") (class "Default")
      (node (ref "R15") (pin "1") (pinfunction "1_1") (pintype "passive"))
      (node (ref "R19") (pin "2") (pinfunction "2_2") (pintype "passive"))
      (node (ref "X1") (pin "12") (pinfunction "S_12") (pintype "passive"))
    )
    (net (code "65") (name "Net-(X1E-S)") (class "Default")
      (node (ref "R20") (pin "1") (pinfunction "1_1") (pintype "passive"))
      (node (ref "R24") (pin "2") (pinfunction "2_2") (pintype "passive"))
      (node (ref "X1") (pin "13") (pinfunction "S_13") (pintype "passive"))
    )
    (net (code "66") (name "Net-(X1F-S)") (class "Default")
      (node (ref "R21") (pin "1") (pinfunction "1_1") (pintype "passive"))
      (node (ref "R25") (pin "2") (pinfunction "2_2") (pintype "passive"))
      (node (ref "X1") (pin "14") (pinfunction "S_14") (pintype "passive"))
    )
    (net (code "67") (name "Net-(X1G-S)") (class "Default")
      (node (ref "R22") (pin "1") (pinfunction "1_1") (pintype "passive"))
      (node (ref "R26") (pin "2") (pinfunction "2_2") (pintype "passive"))
      (node (ref "X1") (pin "15") (pinfunction "S_15") (pintype "passive"))
    )
    (net (code "68") (name "Net-(X1H-S)") (class "Default")
      (node (ref "R23") (pin "1") (pinfunction "1_1") (pintype "passive"))
      (node (ref "R27") (pin "2") (pinfunction "2_2") (pintype "passive"))
      (node (ref "X1") (pin "16") (pinfunction "S_16") (pintype "passive"))
    )
    (net (code "69") (name "Net-(X1I-S)") (class "Default")
      (node (ref "R28") (pin "1") (pinfunction "1_1") (pintype "passive"))
      (node (ref "R32") (pin "2") (pinfunction "2_2") (pintype "passive"))
      (node (ref "X1") (pin "17") (pinfunction "S_17") (pintype "passive"))
    )
    (net (code "70") (name "Net-(X1J-S)") (class "Default")
      (node (ref "R29") (pin "1") (pinfunction "1_1") (pintype "passive"))
      (node (ref "R33") (pin "2") (pinfunction "2_2") (pintype "passive"))
      (node (ref "X1") (pin "18") (pinfunction "S_18") (pintype "passive"))
    )
    (net (code "71") (name "Net-(X1K-S)") (class "Default")
      (node (ref "R30") (pin "1") (pinfunction "1_1") (pintype "passive"))
      (node (ref "R34") (pin "2") (pinfunction "2_2") (pintype "passive"))
      (node (ref "X1") (pin "19") (pinfunction "S_19") (pintype "passive"))
    )
    (net (code "72") (name "Net-(X1M-S)") (class "Default")
      (node (ref "R31") (pin "1") (pinfunction "1_1") (pintype "passive"))
      (node (ref "R35") (pin "2") (pinfunction "2_2") (pintype "passive"))
      (node (ref "X1") (pin "20") (pinfunction "S_20") (pintype "passive"))
    )
    (net (code "73") (name "Net-(X1N-S)") (class "Default")
      (node (ref "X1") (pin "21") (pinfunction "S_21") (pintype "passive"))
      (node (ref "X1") (pin "22") (pinfunction "S_22") (pintype "passive"))
    )
    (net (code "74") (name "Net-(X1P-S)") (class "Default")
      (node (ref "X1") (pin "23") (pinfunction "S_23") (pintype "passive"))
      (node (ref "X1") (pin "24") (pinfunction "S_24") (pintype "passive"))
    )
    (net (code "75") (name "Net-(X1R-S)") (class "Default")
      (node (ref "X1") (pin "25") (pinfunction "S_25") (pintype "passive"))
      (node (ref "X1") (pin "26") (pinfunction "S_26") (pintype "passive"))
    )
    (net (code "76") (name "Net-(X1T-S)") (class "Default")
      (node (ref "JP1") (pin "1") (pinfunction "1_1") (pintype "passive"))
      (node (ref "R1") (pin "1") (pinfunction "1_1") (pintype "passive"))
      (node (ref "X1") (pin "3") (pinfunction "S_3") (pintype "passive"))
    )
    (net (code "77") (name "Net-(X1U-S)") (class "Default")
      (node (ref "JP1") (pin "2") (pinfunction "2_2") (pintype "passive"))
      (node (ref "R2") (pin "1") (pinfunction "1_1") (pintype "passive"))
      (node (ref "X1") (pin "4") (pinfunction "S_4") (pintype "passive"))
    )
    (net (code "78") (name "Net-(X1V-S)") (class "Default")
      (node (ref "R4") (pin "1") (pinfunction "1_1") (pintype "passive"))
      (node (ref "R8") (pin "2") (pinfunction "2_2") (pintype "passive"))
      (node (ref "X1") (pin "5") (pinfunction "S_5") (pintype "passive"))
    )
    (net (code "79") (name "Net-(X1W-S)") (class "Default")
      (node (ref "R5") (pin "1") (pinfunction "1_1") (pintype "passive"))
      (node (ref "R9") (pin "2") (pinfunction "2_2") (pintype "passive"))
      (node (ref "X1") (pin "6") (pinfunction "S_6") (pintype "passive"))
    )
    (net (code "80") (name "Net-(X1X-S)") (class "Default")
      (node (ref "R10") (pin "2") (pinfunction "2_2") (pintype "passive"))
      (node (ref "R6") (pin "1") (pinfunction "1_1") (pintype "passive"))
      (node (ref "X1") (pin "7") (pinfunction "S_7") (pintype "passive"))
    )
    (net (code "81") (name "Net-(X1Y-S)") (class "Default")
      (node (ref "R11") (pin "2") (pinfunction "2_2") (pintype "passive"))
      (node (ref "R7") (pin "1") (pinfunction "1_1") (pintype "passive"))
      (node (ref "X1") (pin "8") (pinfunction "S_8") (pintype "passive"))
    )
    (net (code "82") (name "Net-(X1Z-S)") (class "Default")
      (node (ref "R12") (pin "1") (pinfunction "1_1") (pintype "passive"))
      (node (ref "R16") (pin "2") (pinfunction "2_2") (pintype "passive"))
      (node (ref "X1") (pin "9") (pinfunction "S_9") (pintype "passive"))
    )
    (net (code "83") (name "unconnected-(JP2-Pad1)") (class "Default")
      (node (ref "JP2") (pin "1") (pinfunction "1_1") (pintype "passive"))
    )
    (net (code "84") (name "unconnected-(JP2-Pad2)") (class "Default")
      (node (ref "JP2") (pin "2") (pinfunction "2_2") (pintype "passive"))
    )
    (net (code "85") (name "unconnected-(JP2-Pad3)") (class "Default")
      (node (ref "JP2") (pin "3") (pinfunction "3_3") (pintype "passive"))
    )
    (net (code "86") (name "unconnected-(JP2-Pad4)") (class "Default")
      (node (ref "JP2") (pin "4") (pinfunction "4_4") (pintype "passive"))
    )
    (net (code "87") (name "unconnected-(JP2-Pad5)") (class "Default")
      (node (ref "JP2") (pin "5") (pinfunction "5_5") (pintype "passive"))
    )
    (net (code "88") (name "unconnected-(JP2-Pad6)") (class "Default")
      (node (ref "JP2") (pin "6") (pinfunction "6_6") (pintype "passive"))
    )
    (net (code "89") (name "unconnected-(JP2-Pad7)") (class "Default")
      (node (ref "JP2") (pin "7") (pinfunction "7_7") (pintype "passive"))
    )
    (net (code "90") (name "unconnected-(JP2-Pad8)") (class "Default")
      (node (ref "JP2") (pin "8") (pinfunction "8_8") (pintype "passive"))
    )
    (net (code "91") (name "unconnected-(JP2-Pad9)") (class "Default")
      (node (ref "JP2") (pin "9") (pinfunction "9_9") (pintype "passive"))
    )
    (net (code "92") (name "unconnected-(JP2-Pad10)") (class "Default")
      (node (ref "JP2") (pin "10") (pinfunction "10_10") (pintype "passive"))
    )
    (net (code "93") (name "unconnected-(JP2-Pad12)") (class "Default")
      (node (ref "JP2") (pin "12") (pinfunction "12_12") (pintype "passive"))
    )
    (net (code "94") (name "unconnected-(JP2-Pad14)") (class "Default")
      (node (ref "JP2") (pin "14") (pinfunction "14_14") (pintype "passive"))
    )
    (net (code "95") (name "unconnected-(JP2-Pad15)") (class "Default")
      (node (ref "JP2") (pin "15") (pinfunction "15_15") (pintype "passive"))
    )
    (net (code "96") (name "unconnected-(JP2-Pad16)") (class "Default")
      (node (ref "JP2") (pin "16") (pinfunction "16_16") (pintype "passive"))
    )
    (net (code "97") (name "unconnected-(JP2-Pad17)") (class "Default")
      (node (ref "JP2") (pin "17") (pinfunction "17_17") (pintype "passive"))
    )
    (net (code "98") (name "unconnected-(JP2-Pad18)") (class "Default")
      (node (ref "JP2") (pin "18") (pinfunction "18_18") (pintype "passive"))
    )
    (net (code "99") (name "unconnected-(JP2-Pad19)") (class "Default")
      (node (ref "JP2") (pin "19") (pinfunction "19_19") (pintype "passive"))
    )
    (net (code "100") (name "unconnected-(JP2-Pad20)") (class "Default")
      (node (ref "JP2") (pin "20") (pinfunction "20_20") (pintype "passive"))
    )
    (net (code "101") (name "unconnected-(JP2-Pad21)") (class "Default")
      (node (ref "JP2") (pin "21") (pinfunction "21_21") (pintype "passive"))
    )
    (net (code "102") (name "unconnected-(JP2-Pad22)") (class "Default")
      (node (ref "JP2") (pin "22") (pinfunction "22_22") (pintype "passive"))
    )
    (net (code "103") (name "unconnected-(JP2-Pad23)") (class "Default")
      (node (ref "JP2") (pin "23") (pinfunction "23_23") (pintype "passive"))
    )
    (net (code "104") (name "unconnected-(JP2-Pad24)") (class "Default")
      (node (ref "JP2") (pin "24") (pinfunction "24_24") (pintype "passive"))
    )
    (net (code "105") (name "unconnected-(JP2-Pad25)") (class "Default")
      (node (ref "JP2") (pin "25") (pinfunction "25_25") (pintype "passive"))
    )
    (net (code "106") (name "unconnected-(JP2-Pad26)") (class "Default")
      (node (ref "JP2") (pin "26") (pinfunction "26_26") (pintype "passive"))
    )
    (net (code "107") (name "unconnected-(JP2-Pad27)") (class "Default")
      (node (ref "JP2") (pin "27") (pinfunction "27_27") (pintype "passive"))
    )
    (net (code "108") (name "unconnected-(JP2-Pad28)") (class "Default")
      (node (ref "JP2") (pin "28") (pinfunction "28_28") (pintype "passive"))
    )
    (net (code "109") (name "unconnected-(JP2-Pad29)") (class "Default")
      (node (ref "JP2") (pin "29") (pinfunction "29_29") (pintype "passive"))
    )
    (net (code "110") (name "unconnected-(JP2-Pad30)") (class "Default")
      (node (ref "JP2") (pin "30") (pinfunction "30_30") (pintype "passive"))
    )
    (net (code "111") (name "unconnected-(JP2-Pad31)") (class "Default")
      (node (ref "JP2") (pin "31") (pinfunction "31_31") (pintype "passive"))
    )
    (net (code "112") (name "unconnected-(JP2-Pad32)") (class "Default")
      (node (ref "JP2") (pin "32") (pinfunction "32_32") (pintype "passive"))
    )
    (net (code "113") (name "unconnected-(JP2-Pad33)") (class "Default")
      (node (ref "JP2") (pin "33") (pinfunction "33_33") (pintype "passive"))
    )
    (net (code "114") (name "unconnected-(JP2-Pad34)") (class "Default")
      (node (ref "JP2") (pin "34") (pinfunction "34_34") (pintype "passive"))
    )
    (net (code "115") (name "unconnected-(JP2-Pad35)") (class "Default")
      (node (ref "JP2") (pin "35") (pinfunction "35_35") (pintype "passive"))
    )
    (net (code "116") (name "unconnected-(JP2-Pad36)") (class "Default")
      (node (ref "JP2") (pin "36") (pinfunction "36_36") (pintype "passive"))
    )
    (net (code "117") (name "unconnected-(JP2-Pad37)") (class "Default")
      (node (ref "JP2") (pin "37") (pinfunction "37_37") (pintype "passive"))
    )
    (net (code "118") (name "unconnected-(JP2-Pad38)") (class "Default")
      (node (ref "JP2") (pin "38") (pinfunction "38_38") (pintype "passive"))
    )
    (net (code "119") (name "unconnected-(JP2-Pad39)") (class "Default")
      (node (ref "JP2") (pin "39") (pinfunction "39_39") (pintype "passive"))
    )
    (net (code "120") (name "unconnected-(JP2-Pad40)") (class "Default")
      (node (ref "JP2") (pin "40") (pinfunction "40_40") (pintype "passive"))
    )
    (net (code "121") (name "unconnected-(JP2-Pad41)") (class "Default")
      (node (ref "JP2") (pin "41") (pinfunction "41_41") (pintype "passive"))
    )
    (net (code "122") (name "unconnected-(JP2-Pad42)") (class "Default")
      (node (ref "JP2") (pin "42") (pinfunction "42_42") (pintype "passive"))
    )
    (net (code "123") (name "unconnected-(JP2-Pad43)") (class "Default")
      (node (ref "JP2") (pin "43") (pinfunction "43_43") (pintype "passive"))
    )
    (net (code "124") (name "unconnected-(JP2-Pad44)") (class "Default")
      (node (ref "JP2") (pin "44") (pinfunction "44_44") (pintype "passive"))
    )
    (net (code "125") (name "unconnected-(JP2-Pad45)") (class "Default")
      (node (ref "JP2") (pin "45") (pinfunction "45_45") (pintype "passive"))
    )
    (net (code "126") (name "unconnected-(JP2-Pad46)") (class "Default")
      (node (ref "JP2") (pin "46") (pinfunction "46_46") (pintype "passive"))
    )
    (net (code "127") (name "unconnected-(JP3-Pad1)") (class "Default")
      (node (ref "JP3") (pin "1") (pinfunction "1_1") (pintype "passive"))
    )
    (net (code "128") (name "unconnected-(JP3-Pad2)") (class "Default")
      (node (ref "JP3") (pin "2") (pinfunction "2_2") (pintype "passive"))
    )
    (net (code "129") (name "unconnected-(JP3-Pad3)") (class "Default")
      (node (ref "JP3") (pin "3") (pinfunction "3_3") (pintype "passive"))
    )
    (net (code "130") (name "unconnected-(JP3-Pad4)") (class "Default")
      (node (ref "JP3") (pin "4") (pinfunction "4_4") (pintype "passive"))
    )
    (net (code "131") (name "unconnected-(JP3-Pad5)") (class "Default")
      (node (ref "JP3") (pin "5") (pinfunction "5_5") (pintype "passive"))
    )
    (net (code "132") (name "unconnected-(JP3-Pad6)") (class "Default")
      (node (ref "JP3") (pin "6") (pinfunction "6_6") (pintype "passive"))
    )
    (net (code "133") (name "unconnected-(JP3-Pad7)") (class "Default")
      (node (ref "JP3") (pin "7") (pinfunction "7_7") (pintype "passive"))
    )
    (net (code "134") (name "unconnected-(JP3-Pad8)") (class "Default")
      (node (ref "JP3") (pin "8") (pinfunction "8_8") (pintype "passive"))
    )
    (net (code "135") (name "unconnected-(JP3-Pad9)") (class "Default")
      (node (ref "JP3") (pin "9") (pinfunction "9_9") (pintype "passive"))
    )
    (net (code "136") (name "unconnected-(JP3-Pad10)") (class "Default")
      (node (ref "JP3") (pin "10") (pinfunction "10_10") (pintype "passive"))
    )
    (net (code "137") (name "unconnected-(JP3-Pad11)") (class "Default")
      (node (ref "JP3") (pin "11") (pinfunction "11_11") (pintype "passive"))
    )
    (net (code "138") (name "unconnected-(JP3-Pad12)") (class "Default")
      (node (ref "JP3") (pin "12") (pinfunction "12_12") (pintype "passive"))
    )
    (net (code "139") (name "unconnected-(JP3-Pad13)") (class "Default")
      (node (ref "JP3") (pin "13") (pinfunction "13_13") (pintype "passive"))
    )
    (net (code "140") (name "unconnected-(JP3-Pad14)") (class "Default")
      (node (ref "JP3") (pin "14") (pinfunction "14_14") (pintype "passive"))
    )
    (net (code "141") (name "unconnected-(JP3-Pad15)") (class "Default")
      (node (ref "JP3") (pin "15") (pinfunction "15_15") (pintype "passive"))
    )
    (net (code "142") (name "unconnected-(JP3-Pad16)") (class "Default")
      (node (ref "JP3") (pin "16") (pinfunction "16_16") (pintype "passive"))
    )
    (net (code "143") (name "unconnected-(JP3-Pad17)") (class "Default")
      (node (ref "JP3") (pin "17") (pinfunction "17_17") (pintype "passive"))
    )
    (net (code "144") (name "unconnected-(JP3-Pad18)") (class "Default")
      (node (ref "JP3") (pin "18") (pinfunction "18_18") (pintype "passive"))
    )
    (net (code "145") (name "unconnected-(JP3-Pad19)") (class "Default")
      (node (ref "JP3") (pin "19") (pinfunction "19_19") (pintype "passive"))
    )
    (net (code "146") (name "unconnected-(JP3-Pad20)") (class "Default")
      (node (ref "JP3") (pin "20") (pinfunction "20_20") (pintype "passive"))
    )
    (net (code "147") (name "unconnected-(JP3-Pad21)") (class "Default")
      (node (ref "JP3") (pin "21") (pinfunction "21_21") (pintype "passive"))
    )
    (net (code "148") (name "unconnected-(JP3-Pad22)") (class "Default")
      (node (ref "JP3") (pin "22") (pinfunction "22_22") (pintype "passive"))
    )
    (net (code "149") (name "unconnected-(JP3-Pad23)") (class "Default")
      (node (ref "JP3") (pin "23") (pinfunction "23_23") (pintype "passive"))
    )
    (net (code "150") (name "unconnected-(JP3-Pad24)") (class "Default")
      (node (ref "JP3") (pin "24") (pinfunction "24_24") (pintype "passive"))
    )
    (net (code "151") (name "unconnected-(JP3-Pad25)") (class "Default")
      (node (ref "JP3") (pin "25") (pinfunction "25_25") (pintype "passive"))
    )
    (net (code "152") (name "unconnected-(JP3-Pad26)") (class "Default")
      (node (ref "JP3") (pin "26") (pinfunction "26_26") (pintype "passive"))
    )
    (net (code "153") (name "unconnected-(JP3-Pad27)") (class "Default")
      (node (ref "JP3") (pin "27") (pinfunction "27_27") (pintype "passive"))
    )
    (net (code "154") (name "unconnected-(JP3-Pad28)") (class "Default")
      (node (ref "JP3") (pin "28") (pinfunction "28_28") (pintype "passive"))
    )
    (net (code "155") (name "unconnected-(JP3-Pad29)") (class "Default")
      (node (ref "JP3") (pin "29") (pinfunction "29_29") (pintype "passive"))
    )
    (net (code "156") (name "unconnected-(JP3-Pad30)") (class "Default")
      (node (ref "JP3") (pin "30") (pinfunction "30_30") (pintype "passive"))
    )
    (net (code "157") (name "unconnected-(JP3-Pad31)") (class "Default")
      (node (ref "JP3") (pin "31") (pinfunction "31_31") (pintype "passive"))
    )
    (net (code "158") (name "unconnected-(JP3-Pad32)") (class "Default")
      (node (ref "JP3") (pin "32") (pinfunction "32_32") (pintype "passive"))
    )
    (net (code "159") (name "unconnected-(JP3-Pad33)") (class "Default")
      (node (ref "JP3") (pin "33") (pinfunction "33_33") (pintype "passive"))
    )
    (net (code "160") (name "unconnected-(JP3-Pad34)") (class "Default")
      (node (ref "JP3") (pin "34") (pinfunction "34_34") (pintype "passive"))
    )
    (net (code "161") (name "unconnected-(JP3-Pad35)") (class "Default")
      (node (ref "JP3") (pin "35") (pinfunction "35_35") (pintype "passive"))
    )
    (net (code "162") (name "unconnected-(JP3-Pad36)") (class "Default")
      (node (ref "JP3") (pin "36") (pinfunction "36_36") (pintype "passive"))
    )
    (net (code "163") (name "unconnected-(JP3-Pad37)") (class "Default")
      (node (ref "JP3") (pin "37") (pinfunction "37_37") (pintype "passive"))
    )
    (net (code "164") (name "unconnected-(JP3-Pad38)") (class "Default")
      (node (ref "JP3") (pin "38") (pinfunction "38_38") (pintype "passive"))
    )
    (net (code "165") (name "unconnected-(JP3-Pad39)") (class "Default")
      (node (ref "JP3") (pin "39") (pinfunction "39_39") (pintype "passive"))
    )
    (net (code "166") (name "unconnected-(JP3-Pad40)") (class "Default")
      (node (ref "JP3") (pin "40") (pinfunction "40_40") (pintype "passive"))
    )
    (net (code "167") (name "unconnected-(JP3-Pad41)") (class "Default")
      (node (ref "JP3") (pin "41") (pinfunction "41_41") (pintype "passive"))
    )
    (net (code "168") (name "unconnected-(JP3-Pad42)") (class "Default")
      (node (ref "JP3") (pin "42") (pinfunction "42_42") (pintype "passive"))
    )
    (net (code "169") (name "unconnected-(JP3-Pad43)") (class "Default")
      (node (ref "JP3") (pin "43") (pinfunction "43_43") (pintype "passive"))
    )
    (net (code "170") (name "unconnected-(JP3-Pad44)") (class "Default")
      (node (ref "JP3") (pin "44") (pinfunction "44_44") (pintype "passive"))
    )
    (net (code "171") (name "unconnected-(JP3-Pad45)") (class "Default")
      (node (ref "JP3") (pin "45") (pinfunction "45_45") (pintype "passive"))
    )
    (net (code "172") (name "unconnected-(JP3-Pad46)") (class "Default")
      (node (ref "JP3") (pin "46") (pinfunction "46_46") (pintype "passive"))
    )
    (net (code "173") (name "unconnected-(JP4-Pad1)") (class "Default")
      (node (ref "JP4") (pin "1") (pinfunction "1_1") (pintype "passive"))
    )
    (net (code "174") (name "unconnected-(JP4-Pad2)") (class "Default")
      (node (ref "JP4") (pin "2") (pinfunction "2_2") (pintype "passive"))
    )
    (net (code "175") (name "unconnected-(JP4-Pad3)") (class "Default")
      (node (ref "JP4") (pin "3") (pinfunction "3_3") (pintype "passive"))
    )
    (net (code "176") (name "unconnected-(JP4-Pad4)") (class "Default")
      (node (ref "JP4") (pin "4") (pinfunction "4_4") (pintype "passive"))
    )
    (net (code "177") (name "unconnected-(JP4-Pad5)") (class "Default")
      (node (ref "JP4") (pin "5") (pinfunction "5_5") (pintype "passive"))
    )
    (net (code "178") (name "unconnected-(JP4-Pad6)") (class "Default")
      (node (ref "JP4") (pin "6") (pinfunction "6_6") (pintype "passive"))
    )
    (net (code "179") (name "unconnected-(JP4-Pad7)") (class "Default")
      (node (ref "JP4") (pin "7") (pinfunction "7_7") (pintype "passive"))
    )
    (net (code "180") (name "unconnected-(JP4-Pad8)") (class "Default")
      (node (ref "JP4") (pin "8") (pinfunction "8_8") (pintype "passive"))
    )
    (net (code "181") (name "unconnected-(JP4-Pad9)") (class "Default")
      (node (ref "JP4") (pin "9") (pinfunction "9_9") (pintype "passive"))
    )
    (net (code "182") (name "unconnected-(JP4-Pad10)") (class "Default")
      (node (ref "JP4") (pin "10") (pinfunction "10_10") (pintype "passive"))
    )
    (net (code "183") (name "unconnected-(JP4-Pad11)") (class "Default")
      (node (ref "JP4") (pin "11") (pinfunction "11_11") (pintype "passive"))
    )
    (net (code "184") (name "unconnected-(JP4-Pad12)") (class "Default")
      (node (ref "JP4") (pin "12") (pinfunction "12_12") (pintype "passive"))
    )
    (net (code "185") (name "unconnected-(JP4-Pad13)") (class "Default")
      (node (ref "JP4") (pin "13") (pinfunction "13_13") (pintype "passive"))
    )
    (net (code "186") (name "unconnected-(JP4-Pad14)") (class "Default")
      (node (ref "JP4") (pin "14") (pinfunction "14_14") (pintype "passive"))
    )
    (net (code "187") (name "unconnected-(JP4-Pad15)") (class "Default")
      (node (ref "JP4") (pin "15") (pinfunction "15_15") (pintype "passive"))
    )
    (net (code "188") (name "unconnected-(JP4-Pad16)") (class "Default")
      (node (ref "JP4") (pin "16") (pinfunction "16_16") (pintype "passive"))
    )
    (net (code "189") (name "unconnected-(JP4-Pad17)") (class "Default")
      (node (ref "JP4") (pin "17") (pinfunction "17_17") (pintype "passive"))
    )
    (net (code "190") (name "unconnected-(JP4-Pad18)") (class "Default")
      (node (ref "JP4") (pin "18") (pinfunction "18_18") (pintype "passive"))
    )
    (net (code "191") (name "unconnected-(JP4-Pad19)") (class "Default")
      (node (ref "JP4") (pin "19") (pinfunction "19_19") (pintype "passive"))
    )
    (net (code "192") (name "unconnected-(JP4-Pad20)") (class "Default")
      (node (ref "JP4") (pin "20") (pinfunction "20_20") (pintype "passive"))
    )
    (net (code "193") (name "unconnected-(JP4-Pad21)") (class "Default")
      (node (ref "JP4") (pin "21") (pinfunction "21_21") (pintype "passive"))
    )
    (net (code "194") (name "unconnected-(JP4-Pad22)") (class "Default")
      (node (ref "JP4") (pin "22") (pinfunction "22_22") (pintype "passive"))
    )
    (net (code "195") (name "unconnected-(JP4-Pad23)") (class "Default")
      (node (ref "JP4") (pin "23") (pinfunction "23_23") (pintype "passive"))
    )
    (net (code "196") (name "unconnected-(JP4-Pad24)") (class "Default")
      (node (ref "JP4") (pin "24") (pinfunction "24_24") (pintype "passive"))
    )
    (net (code "197") (name "unconnected-(JP4-Pad25)") (class "Default")
      (node (ref "JP4") (pin "25") (pinfunction "25_25") (pintype "passive"))
    )
    (net (code "198") (name "unconnected-(JP4-Pad26)") (class "Default")
      (node (ref "JP4") (pin "26") (pinfunction "26_26") (pintype "passive"))
    )
    (net (code "199") (name "unconnected-(JP4-Pad27)") (class "Default")
      (node (ref "JP4") (pin "27") (pinfunction "27_27") (pintype "passive"))
    )
    (net (code "200") (name "unconnected-(JP4-Pad28)") (class "Default")
      (node (ref "JP4") (pin "28") (pinfunction "28_28") (pintype "passive"))
    )
    (net (code "201") (name "unconnected-(JP4-Pad29)") (class "Default")
      (node (ref "JP4") (pin "29") (pinfunction "29_29") (pintype "passive"))
    )
    (net (code "202") (name "unconnected-(JP4-Pad30)") (class "Default")
      (node (ref "JP4") (pin "30") (pinfunction "30_30") (pintype "passive"))
    )
    (net (code "203") (name "unconnected-(JP4-Pad31)") (class "Default")
      (node (ref "JP4") (pin "31") (pinfunction "31_31") (pintype "passive"))
    )
    (net (code "204") (name "unconnected-(JP4-Pad32)") (class "Default")
      (node (ref "JP4") (pin "32") (pinfunction "32_32") (pintype "passive"))
    )
    (net (code "205") (name "unconnected-(JP4-Pad33)") (class "Default")
      (node (ref "JP4") (pin "33") (pinfunction "33_33") (pintype "passive"))
    )
    (net (code "206") (name "unconnected-(JP4-Pad34)") (class "Default")
      (node (ref "JP4") (pin "34") (pinfunction "34_34") (pintype "passive"))
    )
    (net (code "207") (name "unconnected-(JP4-Pad35)") (class "Default")
      (node (ref "JP4") (pin "35") (pinfunction "35_35") (pintype "passive"))
    )
    (net (code "208") (name "unconnected-(JP4-Pad36)") (class "Default")
      (node (ref "JP4") (pin "36") (pinfunction "36_36") (pintype "passive"))
    )
    (net (code "209") (name "unconnected-(JP4-Pad37)") (class "Default")
      (node (ref "JP4") (pin "37") (pinfunction "37_37") (pintype "passive"))
    )
    (net (code "210") (name "unconnected-(JP4-Pad38)") (class "Default")
      (node (ref "JP4") (pin "38") (pinfunction "38_38") (pintype "passive"))
    )
    (net (code "211") (name "unconnected-(JP4-Pad39)") (class "Default")
      (node (ref "JP4") (pin "39") (pinfunction "39_39") (pintype "passive"))
    )
    (net (code "212") (name "unconnected-(JP4-Pad40)") (class "Default")
      (node (ref "JP4") (pin "40") (pinfunction "40_40") (pintype "passive"))
    )
    (net (code "213") (name "unconnected-(JP4-Pad41)") (class "Default")
      (node (ref "JP4") (pin "41") (pinfunction "41_41") (pintype "passive"))
    )
    (net (code "214") (name "unconnected-(JP4-Pad42)") (class "Default")
      (node (ref "JP4") (pin "42") (pinfunction "42_42") (pintype "passive"))
    )
    (net (code "215") (name "unconnected-(JP4-Pad43)") (class "Default")
      (node (ref "JP4") (pin "43") (pinfunction "43_43") (pintype "passive"))
    )
    (net (code "216") (name "unconnected-(JP4-Pad44)") (class "Default")
      (node (ref "JP4") (pin "44") (pinfunction "44_44") (pintype "passive"))
    )
    (net (code "217") (name "unconnected-(JP4-Pad45)") (class "Default")
      (node (ref "JP4") (pin "45") (pinfunction "45_45") (pintype "passive"))
    )
    (net (code "218") (name "unconnected-(JP4-Pad46)") (class "Default")
      (node (ref "JP4") (pin "46") (pinfunction "46_46") (pintype "passive"))
    )
  )
)
